# Power.net
KiCad netlist of a schematic drawn in Altium Designer
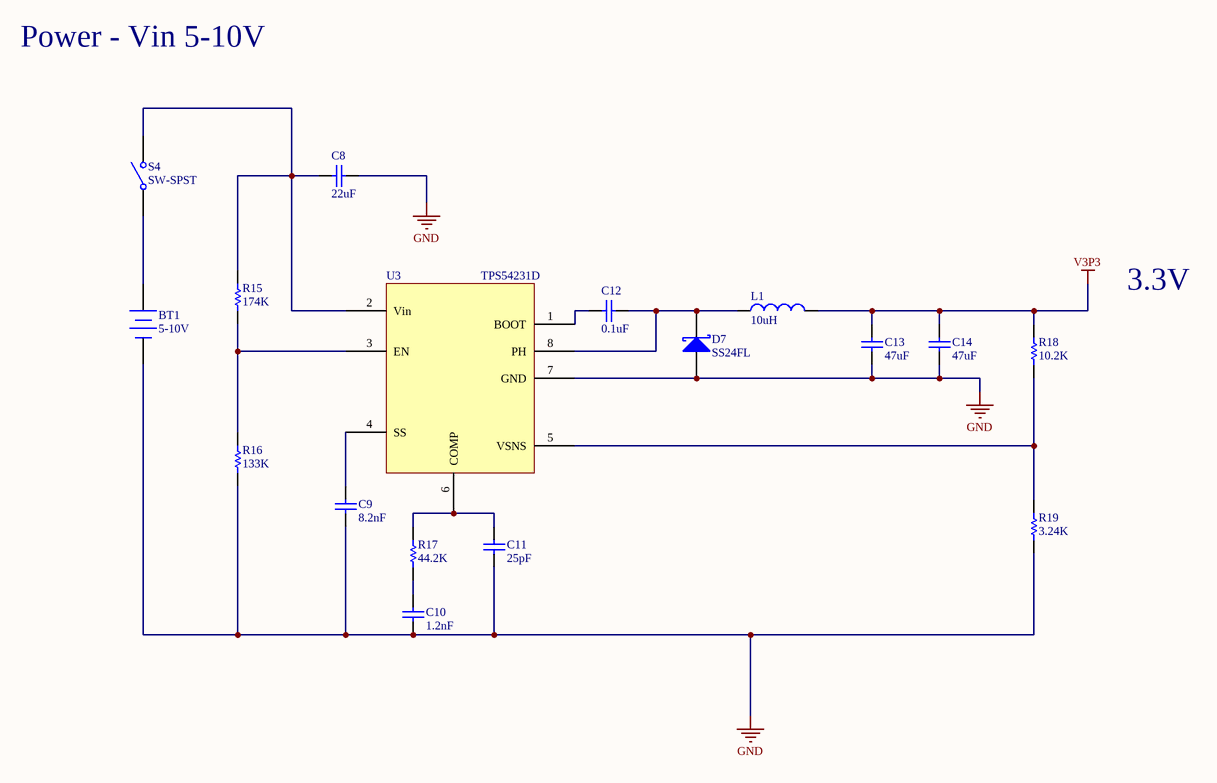
[diagram p0: Power.SchDoc]

(export (version "E")
  (design (tool "Eeschema 10.0.6"))
  (components
    (comp (ref "BT1")
      (value "5-10V")
      (footprint "BAT-2")
      (description "4xAA")
      (libsource (lib "Miscellaneous Devices") (part "Battery"))
    )
    (comp (ref "C8")
      (value "22uF")
      (footprint "own_0603")
      (description "Capacitor")
      (libsource (lib "Miscellaneous Devices") (part "Cap"))
    )
    (comp (ref "C9")
      (value "8.2nF")
      (footprint "own_0603")
      (description "Capacitor")
      (libsource (lib "Miscellaneous Devices") (part "Cap"))
    )
    (comp (ref "C10")
      (value "1.2nF")
      (footprint "own_0603")
      (description "Capacitor")
      (libsource (lib "Miscellaneous Devices") (part "Cap"))
    )
    (comp (ref "C11")
      (value "25pF")
      (footprint "own_0603")
      (description "Capacitor")
      (libsource (lib "Miscellaneous Devices") (part "Cap"))
    )
    (comp (ref "C12")
      (value "0.1uF")
      (footprint "own_0603")
      (description "Capacitor")
      (libsource (lib "Miscellaneous Devices") (part "Cap"))
    )
    (comp (ref "C13")
      (value "47uF")
      (footprint "Own_0805")
      (description "Capacitor")
      (libsource (lib "Miscellaneous Devices") (part "Cap"))
    )
    (comp (ref "C14")
      (value "47uF")
      (footprint "Own_0805")
      (description "Capacitor")
      (libsource (lib "Miscellaneous Devices") (part "Cap"))
    )
    (comp (ref "D7")
      (value "SS24FL")
      (footprint "ShotkyCMS")
      (description "Schottky Rectifier")
      (libsource (lib "Miscellaneous Devices") (part "Diode 10TQ035"))
    )
    (comp (ref "L1")
      (value "10uH")
      (footprint "Inductor CMS")
      (description "Inductor")
      (libsource (lib "Miscellaneous Devices") (part "Inductor"))
    )
    (comp (ref "R15")
      (value "174K")
      (footprint "own_0603")
      (description "Resistor")
      (libsource (lib "Miscellaneous Devices") (part "Res1"))
    )
    (comp (ref "R16")
      (value "133K")
      (footprint "own_0603")
      (description "Resistor")
      (libsource (lib "Miscellaneous Devices") (part "Res1"))
    )
    (comp (ref "R17")
      (value "44.2K")
      (footprint "own_0603")
      (description "Resistor")
      (libsource (lib "Miscellaneous Devices") (part "Res1"))
    )
    (comp (ref "R18")
      (value "10.2K")
      (footprint "own_0603")
      (description "Resistor")
      (libsource (lib "Miscellaneous Devices") (part "Res1"))
    )
    (comp (ref "R19")
      (value "3.24K")
      (footprint "own_0603")
      (description "Resistor")
      (libsource (lib "Miscellaneous Devices") (part "Res1"))
    )
    (comp (ref "S4")
      (value "SW-SPST")
      (footprint "SPST-2")
      (description "Single-Pole, Single-Throw Switch")
      (libsource (lib "Miscellaneous Devices") (part "SW-SPST"))
    )
    (comp (ref "U3")
      (value "TPS54231D")
      (footprint "R-PDSO-G8")
      (description "Buck SD 3.3V")
      (libsource (lib "Schlib") (part "TPS54231D"))
    )
  )
  (nets
    (net (code "1") (name "GND") (class "Default")
      (node (ref "BT1") (pin "2") (pinfunction "-_2") (pintype "passive"))
      (node (ref "C10") (pin "1") (pinfunction "1_1") (pintype "passive"))
      (node (ref "C11") (pin "1") (pinfunction "1_1") (pintype "passive"))
      (node (ref "C13") (pin "1") (pinfunction "1_1") (pintype "passive"))
      (node (ref "C14") (pin "1") (pinfunction "1_1") (pintype "passive"))
      (node (ref "C8") (pin "2") (pinfunction "2_2") (pintype "passive"))
      (node (ref "C9") (pin "1") (pinfunction "1_1") (pintype "passive"))
      (node (ref "D7") (pin "2") (pinfunction "A_2") (pintype "passive"))
      (node (ref "R16") (pin "2") (pinfunction "2_2") (pintype "passive"))
      (node (ref "R19") (pin "2") (pinfunction "2_2") (pintype "passive"))
      (node (ref "U3") (pin "7") (pinfunction "GND_7") (pintype "passive"))
    )
    (net (code "2") (name "Net-(BT1-+)") (class "Default")
      (node (ref "BT1") (pin "1") (pinfunction "+_1") (pintype "passive"))
      (node (ref "S4") (pin "1") (pinfunction "COMMON_1") (pintype "passive"))
    )
    (net (code "3") (name "Net-(C10-Pad2)") (class "Default")
      (node (ref "C10") (pin "2") (pinfunction "2_2") (pintype "passive"))
      (node (ref "R17") (pin "2") (pinfunction "2_2") (pintype "passive"))
    )
    (net (code "4") (name "Net-(D7-K)") (class "Default")
      (node (ref "C12") (pin "1") (pinfunction "1_1") (pintype "passive"))
      (node (ref "D7") (pin "1") (pinfunction "K_1") (pintype "passive"))
      (node (ref "L1") (pin "1") (pinfunction "1_1") (pintype "passive"))
      (node (ref "U3") (pin "8") (pinfunction "PH_8") (pintype "passive"))
    )
    (net (code "5") (name "Net-(S4-NO)") (class "Default")
      (node (ref "C8") (pin "1") (pinfunction "1_1") (pintype "passive"))
      (node (ref "R15") (pin "1") (pinfunction "1_1") (pintype "passive"))
      (node (ref "S4") (pin "2") (pinfunction "NO_2") (pintype "passive"))
      (node (ref "U3") (pin "2") (pinfunction "Vin_2") (pintype "passive"))
    )
    (net (code "6") (name "Net-(U3-BOOT)") (class "Default")
      (node (ref "C12") (pin "2") (pinfunction "2_2") (pintype "passive"))
      (node (ref "U3") (pin "1") (pinfunction "BOOT_1") (pintype "passive"))
    )
    (net (code "7") (name "Net-(U3-COMP)") (class "Default")
      (node (ref "C11") (pin "2") (pinfunction "2_2") (pintype "passive"))
      (node (ref "R17") (pin "1") (pinfunction "1_1") (pintype "passive"))
      (node (ref "U3") (pin "6") (pinfunction "COMP_6") (pintype "passive"))
    )
    (net (code "8") (name "Net-(U3-EN)") (class "Default")
      (node (ref "R15") (pin "2") (pinfunction "2_2") (pintype "passive"))
      (node (ref "R16") (pin "1") (pinfunction "1_1") (pintype "passive"))
      (node (ref "U3") (pin "3") (pinfunction "EN_3") (pintype "passive"))
    )
    (net (code "9") (name "Net-(U3-SS)") (class "Default")
      (node (ref "C9") (pin "2") (pinfunction "2_2") (pintype "passive"))
      (node (ref "U3") (pin "4") (pinfunction "SS_4") (pintype "passive"))
    )
    (net (code "10") (name "Net-(U3-VSNS)") (class "Default")
      (node (ref "R18") (pin "2") (pinfunction "2_2") (pintype "passive"))
      (node (ref "R19") (pin "1") (pinfunction "1_1") (pintype "passive"))
      (node (ref "U3") (pin "5") (pinfunction "VSNS_5") (pintype "passive"))
    )
    (net (code "11") (name "V3P3") (class "Default")
      (node (ref "C13") (pin "2") (pinfunction "2_2") (pintype "passive"))
      (node (ref "C14") (pin "2") (pinfunction "2_2") (pintype "passive"))
      (node (ref "L1") (pin "2") (pinfunction "2_2") (pintype "passive"))
      (node (ref "R18") (pin "1") (pinfunction "1_1") (pintype "passive"))
    )
  )
)
